# AD5293.net
KiCad netlist of a schematic drawn in EasyEDA Pro
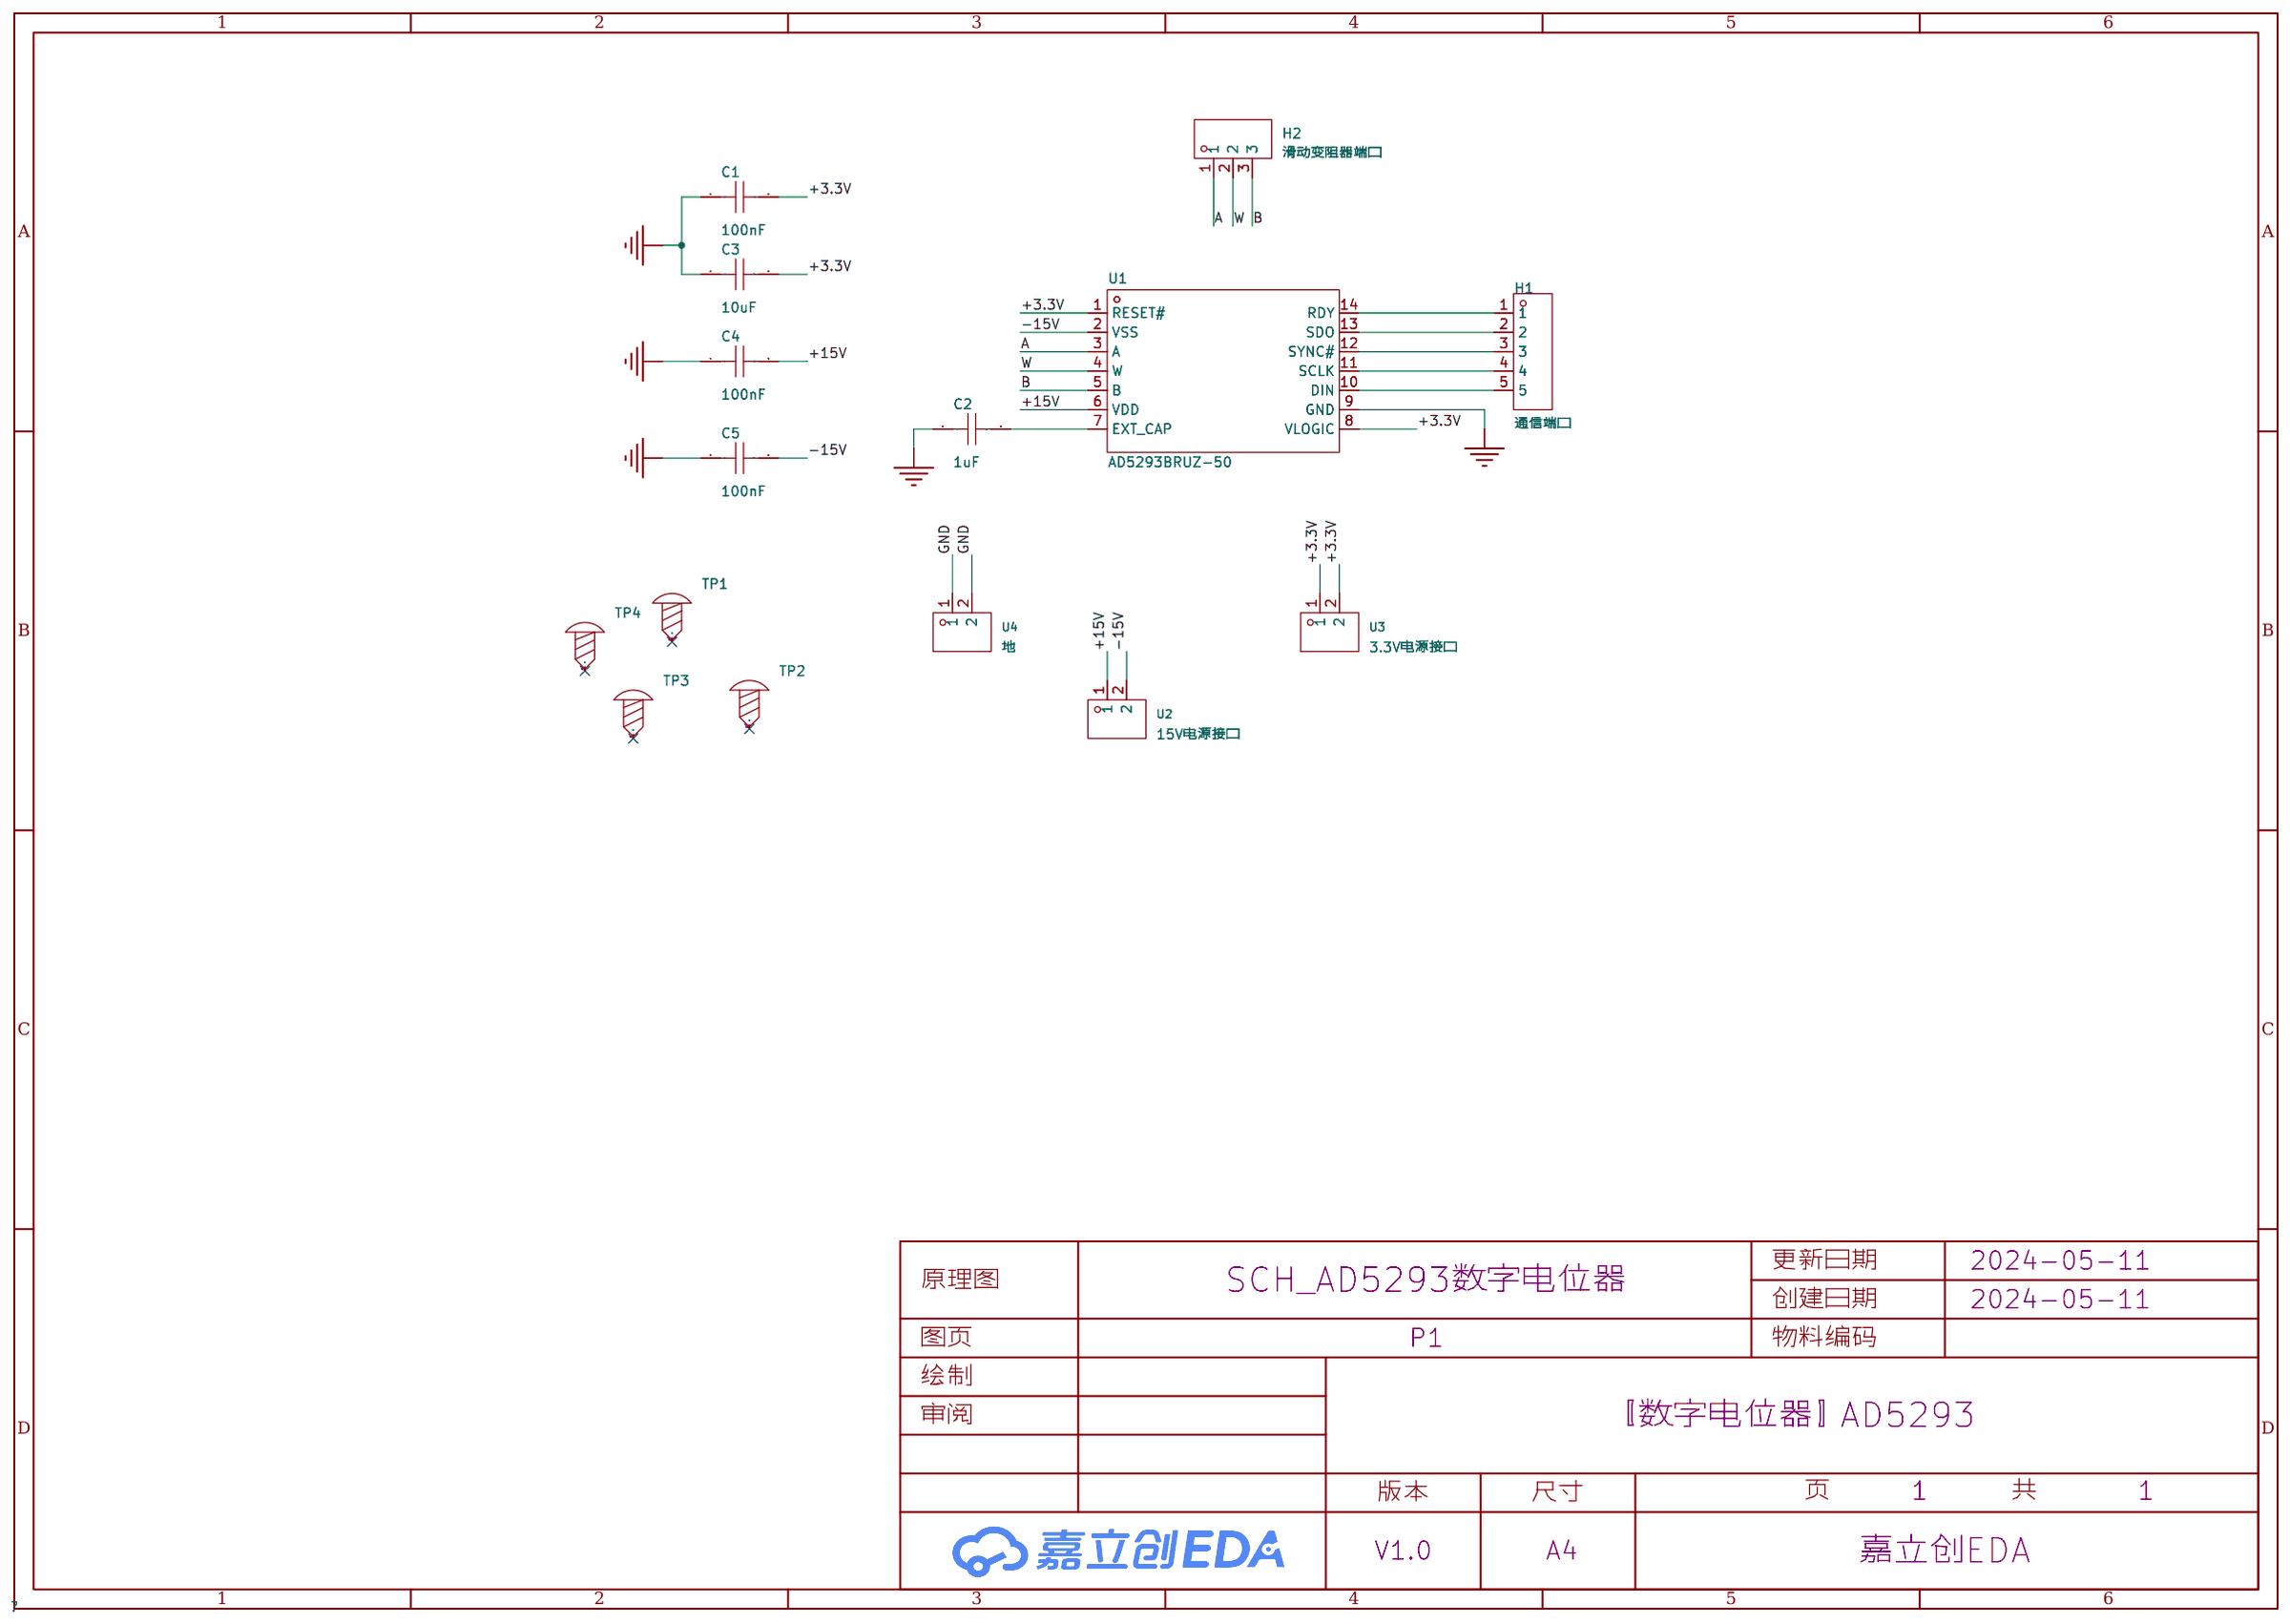
[diagram p0: schematic sheet]

(export (version "E")
  (design (tool "Eeschema 10.0.6"))
  (components
    (comp (ref "C1")
      (value "100nF")
      (footprint "easyedapro:C0603")
      (fields
        (field (name "Manufacturer Part") "CC0603KRX7R9BB104")
        (field (name "Manufacturer") "YAGEO(国巨)")
      )
      (libsource (lib "easyedapro") (part "CapAcitance"))
    )
    (comp (ref "C2")
      (value "1uF")
      (footprint "easyedapro:C0603")
      (fields
        (field (name "Manufacturer Part") "CL10A105KB8NNNC")
        (field (name "Manufacturer") "SAMSUNG(三星)")
      )
      (libsource (lib "easyedapro") (part "CapAcitance"))
    )
    (comp (ref "C3")
      (value "10uF")
      (footprint "easyedapro:C0603")
      (fields
        (field (name "Manufacturer Part") "CL21A106KOQNNNE")
        (field (name "Manufacturer") "SAMSUNG(三星)")
      )
      (libsource (lib "easyedapro") (part "CapAcitance"))
    )
    (comp (ref "C4")
      (value "100nF")
      (footprint "easyedapro:C0603")
      (fields
        (field (name "Manufacturer Part") "CC0603KRX7R9BB104")
        (field (name "Manufacturer") "YAGEO(国巨)")
      )
      (libsource (lib "easyedapro") (part "CapAcitance"))
    )
    (comp (ref "C5")
      (value "100nF")
      (footprint "easyedapro:C0603")
      (fields
        (field (name "Manufacturer Part") "CC0603KRX7R9BB104")
        (field (name "Manufacturer") "YAGEO(国巨)")
      )
      (libsource (lib "easyedapro") (part "CapAcitance"))
    )
    (comp (ref "H1")
      (value "通信端口")
      (footprint "easyedapro:HDR-TH_5P-P2.54-V-M")
      (fields (field (name "Manufacturer") "kinghelm(金航标)"))
      (libsource (lib "easyedapro") (part "KH-2.54PH180-1X5P-L11.5"))
    )
    (comp (ref "H2")
      (value "滑动变阻器端口")
      (footprint "easyedapro:HDR-TH_3P-P2.54-V-M")
      (fields (field (name "Manufacturer") "kinghelm(金航标)"))
      (libsource (lib "easyedapro") (part "KH-2.54PH180-1X3P-L11.5"))
    )
    (comp (ref "TP1") (value "~") (footprint "easyedapro:M2螺丝") (libsource (lib "easyedapro") (part "螺丝孔")))
    (comp (ref "TP2") (value "~") (footprint "easyedapro:M2螺丝") (libsource (lib "easyedapro") (part "螺丝孔")))
    (comp (ref "TP3") (value "~") (footprint "easyedapro:M2螺丝") (libsource (lib "easyedapro") (part "螺丝孔")))
    (comp (ref "TP4") (value "~") (footprint "easyedapro:M2螺丝") (libsource (lib "easyedapro") (part "螺丝孔")))
    (comp (ref "U1")
      (value "AD5293BRUZ-50")
      (footprint "easyedapro:TSSOP-14_L5.0-W4.4-P0.65-LS6.4-BL")
      (description "电阻值(欧姆):50kΩ;接口类型:SPI;供电电压:9V~33V；9V~16.5V;精度:±1%;")
      (fields (field (name "Manufacturer") "ADI(亚德诺)"))
      (libsource (lib "easyedapro") (part "AD5293BRUZ-50"))
    )
    (comp (ref "U2")
      (value "15V电源接口")
      (footprint "easyedapro:HDR-TH_2P-P2.54-V-M")
      (description "插针结构:1x2P;间距:2.54mm;行距:2.54mm;圆针/方针:方针;安装类型:直插;排数:单排;总PIN位数:2P;额定电流:3A;工作温度范围:-40°C~+105°C;")
      (fields (field (name "Manufacturer") "GREENCONN(格康)"))
      (libsource (lib "easyedapro") (part "GPHA101-0202A001A1BA"))
    )
    (comp (ref "U3")
      (value "3.3V电源接口")
      (footprint "easyedapro:HDR-TH_2P-P2.54-V-M")
      (description "插针结构:1x2P;间距:2.54mm;行距:2.54mm;圆针/方针:方针;安装类型:直插;排数:单排;总PIN位数:2P;额定电流:3A;工作温度范围:-40°C~+105°C;")
      (fields (field (name "Manufacturer") "GREENCONN(格康)"))
      (libsource (lib "easyedapro") (part "GPHA101-0202A001A1BA"))
    )
    (comp (ref "U4")
      (value "地")
      (footprint "easyedapro:HDR-TH_2P-P2.54-V-M")
      (description "插针结构:1x2P;间距:2.54mm;行距:2.54mm;圆针/方针:方针;安装类型:直插;排数:单排;总PIN位数:2P;额定电流:3A;工作温度范围:-40°C~+105°C;")
      (fields (field (name "Manufacturer") "GREENCONN(格康)"))
      (libsource (lib "easyedapro") (part "GPHA101-0202A001A1BA"))
    )
  )
  (nets
    (net (code "1") (name "/+3.3V") (class "Default")
      (node (ref "C1") (pin "2") (pinfunction "2_2") (pintype "input"))
      (node (ref "C3") (pin "2") (pinfunction "2_2") (pintype "input"))
      (node (ref "U1") (pin "1") (pinfunction "RESET#_1") (pintype "unspecified"))
      (node (ref "U1") (pin "8") (pinfunction "VLOGIC_8") (pintype "unspecified"))
      (node (ref "U3") (pin "1") (pinfunction "1_1") (pintype "input"))
      (node (ref "U3") (pin "2") (pinfunction "2_2") (pintype "input"))
    )
    (net (code "2") (name "/+15V") (class "Default")
      (node (ref "C4") (pin "2") (pinfunction "2_2") (pintype "input"))
      (node (ref "U1") (pin "6") (pinfunction "VDD_6") (pintype "unspecified"))
      (node (ref "U2") (pin "1") (pinfunction "1_1") (pintype "input"))
    )
    (net (code "3") (name "/-15V") (class "Default")
      (node (ref "C5") (pin "2") (pinfunction "2_2") (pintype "input"))
      (node (ref "U1") (pin "2") (pinfunction "VSS_2") (pintype "unspecified"))
      (node (ref "U2") (pin "2") (pinfunction "2_2") (pintype "input"))
    )
    (net (code "4") (name "/A") (class "Default")
      (node (ref "H2") (pin "1") (pinfunction "1_1") (pintype "unspecified"))
      (node (ref "U1") (pin "3") (pinfunction "A_3") (pintype "unspecified"))
    )
    (net (code "5") (name "/B") (class "Default")
      (node (ref "H2") (pin "3") (pinfunction "3_3") (pintype "unspecified"))
      (node (ref "U1") (pin "5") (pinfunction "B_5") (pintype "unspecified"))
    )
    (net (code "6") (name "/W") (class "Default")
      (node (ref "H2") (pin "2") (pinfunction "2_2") (pintype "unspecified"))
      (node (ref "U1") (pin "4") (pinfunction "W_4") (pintype "unspecified"))
    )
    (net (code "7") (name "GND") (class "Default")
      (node (ref "C1") (pin "1") (pinfunction "1_1") (pintype "input"))
      (node (ref "C2") (pin "1") (pinfunction "1_1") (pintype "input"))
      (node (ref "C3") (pin "1") (pinfunction "1_1") (pintype "input"))
      (node (ref "C4") (pin "1") (pinfunction "1_1") (pintype "input"))
      (node (ref "C5") (pin "1") (pinfunction "1_1") (pintype "input"))
      (node (ref "U1") (pin "9") (pinfunction "GND_9") (pintype "unspecified"))
      (node (ref "U4") (pin "1") (pinfunction "1_1") (pintype "input"))
      (node (ref "U4") (pin "2") (pinfunction "2_2") (pintype "input"))
    )
    (net (code "8") (name "Net-(U1-DIN)") (class "Default")
      (node (ref "H1") (pin "5") (pinfunction "5_5") (pintype "unspecified"))
      (node (ref "U1") (pin "10") (pinfunction "DIN_10") (pintype "unspecified"))
    )
    (net (code "9") (name "Net-(U1-EXT_CAP)") (class "Default")
      (node (ref "C2") (pin "2") (pinfunction "2_2") (pintype "input"))
      (node (ref "U1") (pin "7") (pinfunction "EXT_CAP_7") (pintype "unspecified"))
    )
    (net (code "10") (name "Net-(U1-RDY)") (class "Default")
      (node (ref "H1") (pin "1") (pinfunction "1_1") (pintype "unspecified"))
      (node (ref "U1") (pin "14") (pinfunction "RDY_14") (pintype "unspecified"))
    )
    (net (code "11") (name "Net-(U1-SCLK)") (class "Default")
      (node (ref "H1") (pin "4") (pinfunction "4_4") (pintype "unspecified"))
      (node (ref "U1") (pin "11") (pinfunction "SCLK_11") (pintype "unspecified"))
    )
    (net (code "12") (name "Net-(U1-SDO)") (class "Default")
      (node (ref "H1") (pin "2") (pinfunction "2_2") (pintype "unspecified"))
      (node (ref "U1") (pin "13") (pinfunction "SDO_13") (pintype "unspecified"))
    )
    (net (code "13") (name "Net-(U1-SYNC#)") (class "Default")
      (node (ref "H1") (pin "3") (pinfunction "3_3") (pintype "unspecified"))
      (node (ref "U1") (pin "12") (pinfunction "SYNC#_12") (pintype "unspecified"))
    )
    (net (code "14") (name "unconnected-(TP1-Pad1)") (class "Default")
      (node (ref "TP1") (pin "1") (pinfunction "1_1") (pintype "input+no_connect"))
    )
    (net (code "15") (name "unconnected-(TP2-Pad1)") (class "Default")
      (node (ref "TP2") (pin "1") (pinfunction "1_1") (pintype "input+no_connect"))
    )
    (net (code "16") (name "unconnected-(TP3-Pad1)") (class "Default")
      (node (ref "TP3") (pin "1") (pinfunction "1_1") (pintype "input+no_connect"))
    )
    (net (code "17") (name "unconnected-(TP4-Pad1)") (class "Default")
      (node (ref "TP4") (pin "1") (pinfunction "1_1") (pintype "input+no_connect"))
    )
  )
)
